# 20160303_hello_world.net
KiCad netlist of a schematic drawn in EAGLE
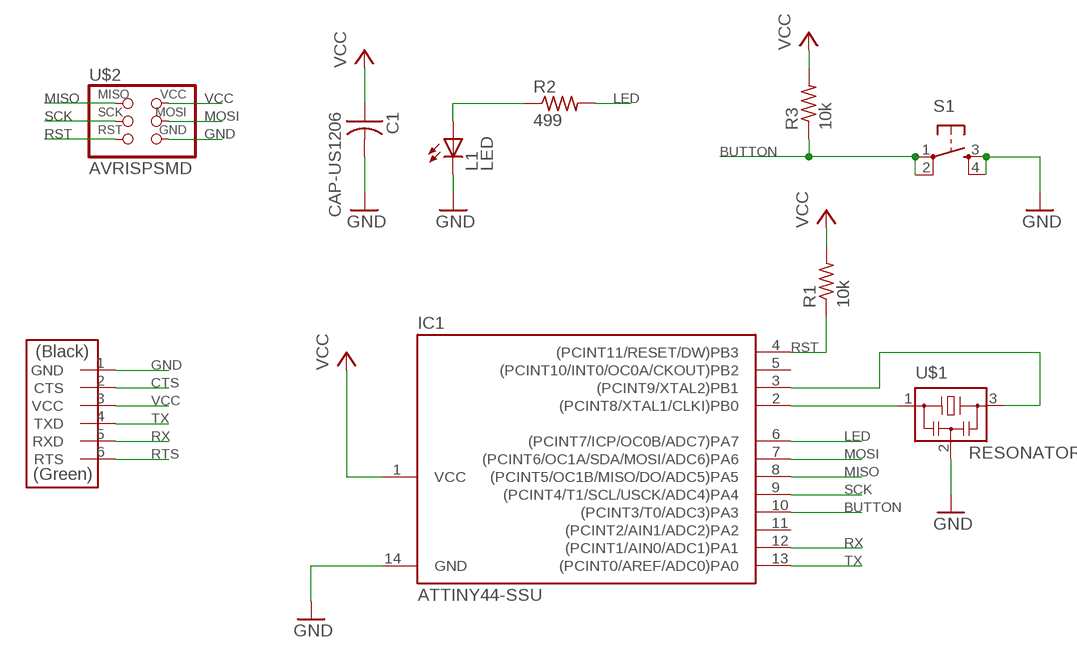
[diagram p0: schematic, sheet 1]

(export (version "E")
  (design (tool "Eeschema 10.0.6"))
  (components
    (comp (ref "C1")
      (value "CAP-US1206")
      (footprint "eagle-import:C1206")
      (libsource (lib "eagle-import") (part "CAP-US1206"))
    )
    (comp (ref "IC1")
      (value "ATTINY44-SSU")
      (footprint "eagle-import:SOIC14")
      (libsource (lib "eagle-import") (part "ATTINY44-SSU"))
    )
    (comp (ref "JP1")
      (value "FTDI-SMD-HEADER")
      (footprint "eagle-import:1X06SMD")
      (libsource (lib "eagle-import") (part "FTDI-SMD-HEADER"))
    )
    (comp (ref "L1")
      (value "LED")
      (footprint "eagle-import:LED1206")
      (libsource (lib "eagle-import") (part "LED"))
    )
    (comp (ref "R1")
      (value "10k")
      (footprint "eagle-import:R1206")
      (libsource (lib "eagle-import") (part "RES-US1206"))
    )
    (comp (ref "R2")
      (value "499")
      (footprint "eagle-import:R1206")
      (libsource (lib "eagle-import") (part "RES-US1206"))
    )
    (comp (ref "R3")
      (value "10k")
      (footprint "eagle-import:R1206")
      (libsource (lib "eagle-import") (part "RES-US1206"))
    )
    (comp (ref "S1")
      (value "6MM_SWITCH6MM_SWITCH")
      (footprint "eagle-import:6MM_SWITCH")
      (libsource (lib "eagle-import") (part "6MM_SWITCH6MM_SWITCH"))
    )
    (comp (ref "U$1")
      (value "RESONATOR")
      (footprint "eagle-import:EFOBM")
      (libsource (lib "eagle-import") (part "RESONATOR"))
    )
    (comp (ref "U$2")
      (value "AVRISPSMD")
      (footprint "eagle-import:2X03SMD")
      (libsource (lib "eagle-import") (part "AVRISPSMD"))
    )
  )
  (nets
    (net (code "1") (name "/BUTTON") (class "Default")
      (node (ref "IC1") (pin "10") (pinfunction "(PCINT3/T0/ADC3)PA3_10") (pintype "bidirectional"))
      (node (ref "R3") (pin "1") (pinfunction "1_1") (pintype "passive"))
      (node (ref "S1") (pin "1") (pinfunction "P_1") (pintype "passive"))
      (node (ref "S1") (pin "2") (pinfunction "P1_2") (pintype "passive"))
    )
    (net (code "2") (name "/CTS") (class "Default")
      (node (ref "JP1") (pin "2") (pinfunction "CTS_2") (pintype "bidirectional"))
    )
    (net (code "3") (name "/LED") (class "Default")
      (node (ref "IC1") (pin "6") (pinfunction "(PCINT7/ICP/OC0B/ADC7)PA7_6") (pintype "bidirectional"))
      (node (ref "R2") (pin "2") (pinfunction "2_2") (pintype "passive"))
    )
    (net (code "4") (name "/MISO") (class "Default")
      (node (ref "IC1") (pin "8") (pinfunction "(PCINT5/OC1B/MISO/DO/ADC5)PA5_8") (pintype "bidirectional"))
      (node (ref "U$2") (pin "1") (pinfunction "MISO_1") (pintype "passive"))
    )
    (net (code "5") (name "/MOSI") (class "Default")
      (node (ref "IC1") (pin "7") (pinfunction "(PCINT6/OC1A/SDA/MOSI/ADC6)PA6_7") (pintype "bidirectional"))
      (node (ref "U$2") (pin "4") (pinfunction "MOSI_4") (pintype "passive"))
    )
    (net (code "6") (name "/RST") (class "Default")
      (node (ref "IC1") (pin "4") (pinfunction "(PCINT11/RESET/DW)PB3_4") (pintype "bidirectional"))
      (node (ref "R1") (pin "1") (pinfunction "1_1") (pintype "passive"))
      (node (ref "U$2") (pin "5") (pinfunction "RST_5") (pintype "passive"))
    )
    (net (code "7") (name "/RTS") (class "Default")
      (node (ref "JP1") (pin "6") (pinfunction "RTS_6") (pintype "bidirectional"))
    )
    (net (code "8") (name "/RX") (class "Default")
      (node (ref "IC1") (pin "12") (pinfunction "(PCINT1/AIN0/ADC1)PA1_12") (pintype "bidirectional"))
      (node (ref "JP1") (pin "5") (pinfunction "RXD_5") (pintype "bidirectional"))
    )
    (net (code "9") (name "/SCK") (class "Default")
      (node (ref "IC1") (pin "9") (pinfunction "(PCINT4/T1/SCL/USCK/ADC4)PA4_9") (pintype "bidirectional"))
      (node (ref "U$2") (pin "3") (pinfunction "SCK_3") (pintype "passive"))
    )
    (net (code "10") (name "/TX") (class "Default")
      (node (ref "IC1") (pin "13") (pinfunction "(PCINT0/AREF/ADC0)PA0_13") (pintype "bidirectional"))
      (node (ref "JP1") (pin "4") (pinfunction "TXD_4") (pintype "bidirectional"))
    )
    (net (code "11") (name "GND") (class "Default")
      (node (ref "C1") (pin "2") (pinfunction "2_2") (pintype "passive"))
      (node (ref "IC1") (pin "14") (pinfunction "GND_14") (pintype "power_in"))
      (node (ref "JP1") (pin "1") (pinfunction "GND_1") (pintype "bidirectional"))
      (node (ref "L1") (pin "2") (pinfunction "C_2") (pintype "passive"))
      (node (ref "S1") (pin "3") (pinfunction "S_3") (pintype "passive"))
      (node (ref "S1") (pin "4") (pinfunction "S1_4") (pintype "passive"))
      (node (ref "U$1") (pin "2") (pinfunction "2_2") (pintype "passive"))
      (node (ref "U$2") (pin "6") (pinfunction "GND_6") (pintype "passive"))
    )
    (net (code "12") (name "Net-(IC1-(PCINT8{slash}XTAL1{slash}CLKI)PB0)") (class "Default")
      (node (ref "IC1") (pin "2") (pinfunction "(PCINT8/XTAL1/CLKI)PB0_2") (pintype "bidirectional"))
      (node (ref "U$1") (pin "1") (pinfunction "1_1") (pintype "passive"))
    )
    (net (code "13") (name "Net-(IC1-(PCINT9{slash}XTAL2)PB1)") (class "Default")
      (node (ref "IC1") (pin "3") (pinfunction "(PCINT9/XTAL2)PB1_3") (pintype "bidirectional"))
      (node (ref "U$1") (pin "3") (pinfunction "3_3") (pintype "passive"))
    )
    (net (code "14") (name "Net-(L1-A)") (class "Default")
      (node (ref "L1") (pin "1") (pinfunction "A_1") (pintype "passive"))
      (node (ref "R2") (pin "1") (pinfunction "1_1") (pintype "passive"))
    )
    (net (code "15") (name "VCC") (class "Default")
      (node (ref "C1") (pin "1") (pinfunction "1_1") (pintype "passive"))
      (node (ref "IC1") (pin "1") (pinfunction "VCC_1") (pintype "power_in"))
      (node (ref "JP1") (pin "3") (pinfunction "VCC_3") (pintype "bidirectional"))
      (node (ref "R1") (pin "2") (pinfunction "2_2") (pintype "passive"))
      (node (ref "R3") (pin "2") (pinfunction "2_2") (pintype "passive"))
      (node (ref "U$2") (pin "2") (pinfunction "VCC_2") (pintype "passive"))
    )
    (net (code "16") (name "unconnected-(IC1-(PCINT2{slash}AIN1{slash}ADC2)PA2-Pad11)") (class "Default")
      (node (ref "IC1") (pin "11") (pinfunction "(PCINT2/AIN1/ADC2)PA2_11") (pintype "bidirectional"))
    )
    (net (code "17") (name "unconnected-(IC1-(PCINT10{slash}INT0{slash}OC0A{slash}CKOUT)PB2-Pad5)") (class "Default")
      (node (ref "IC1") (pin "5") (pinfunction "(PCINT10/INT0/OC0A/CKOUT)PB2_5") (pintype "bidirectional"))
    )
  )
)
